# design.net
KiCad netlist of a schematic drawn in Altium Designer
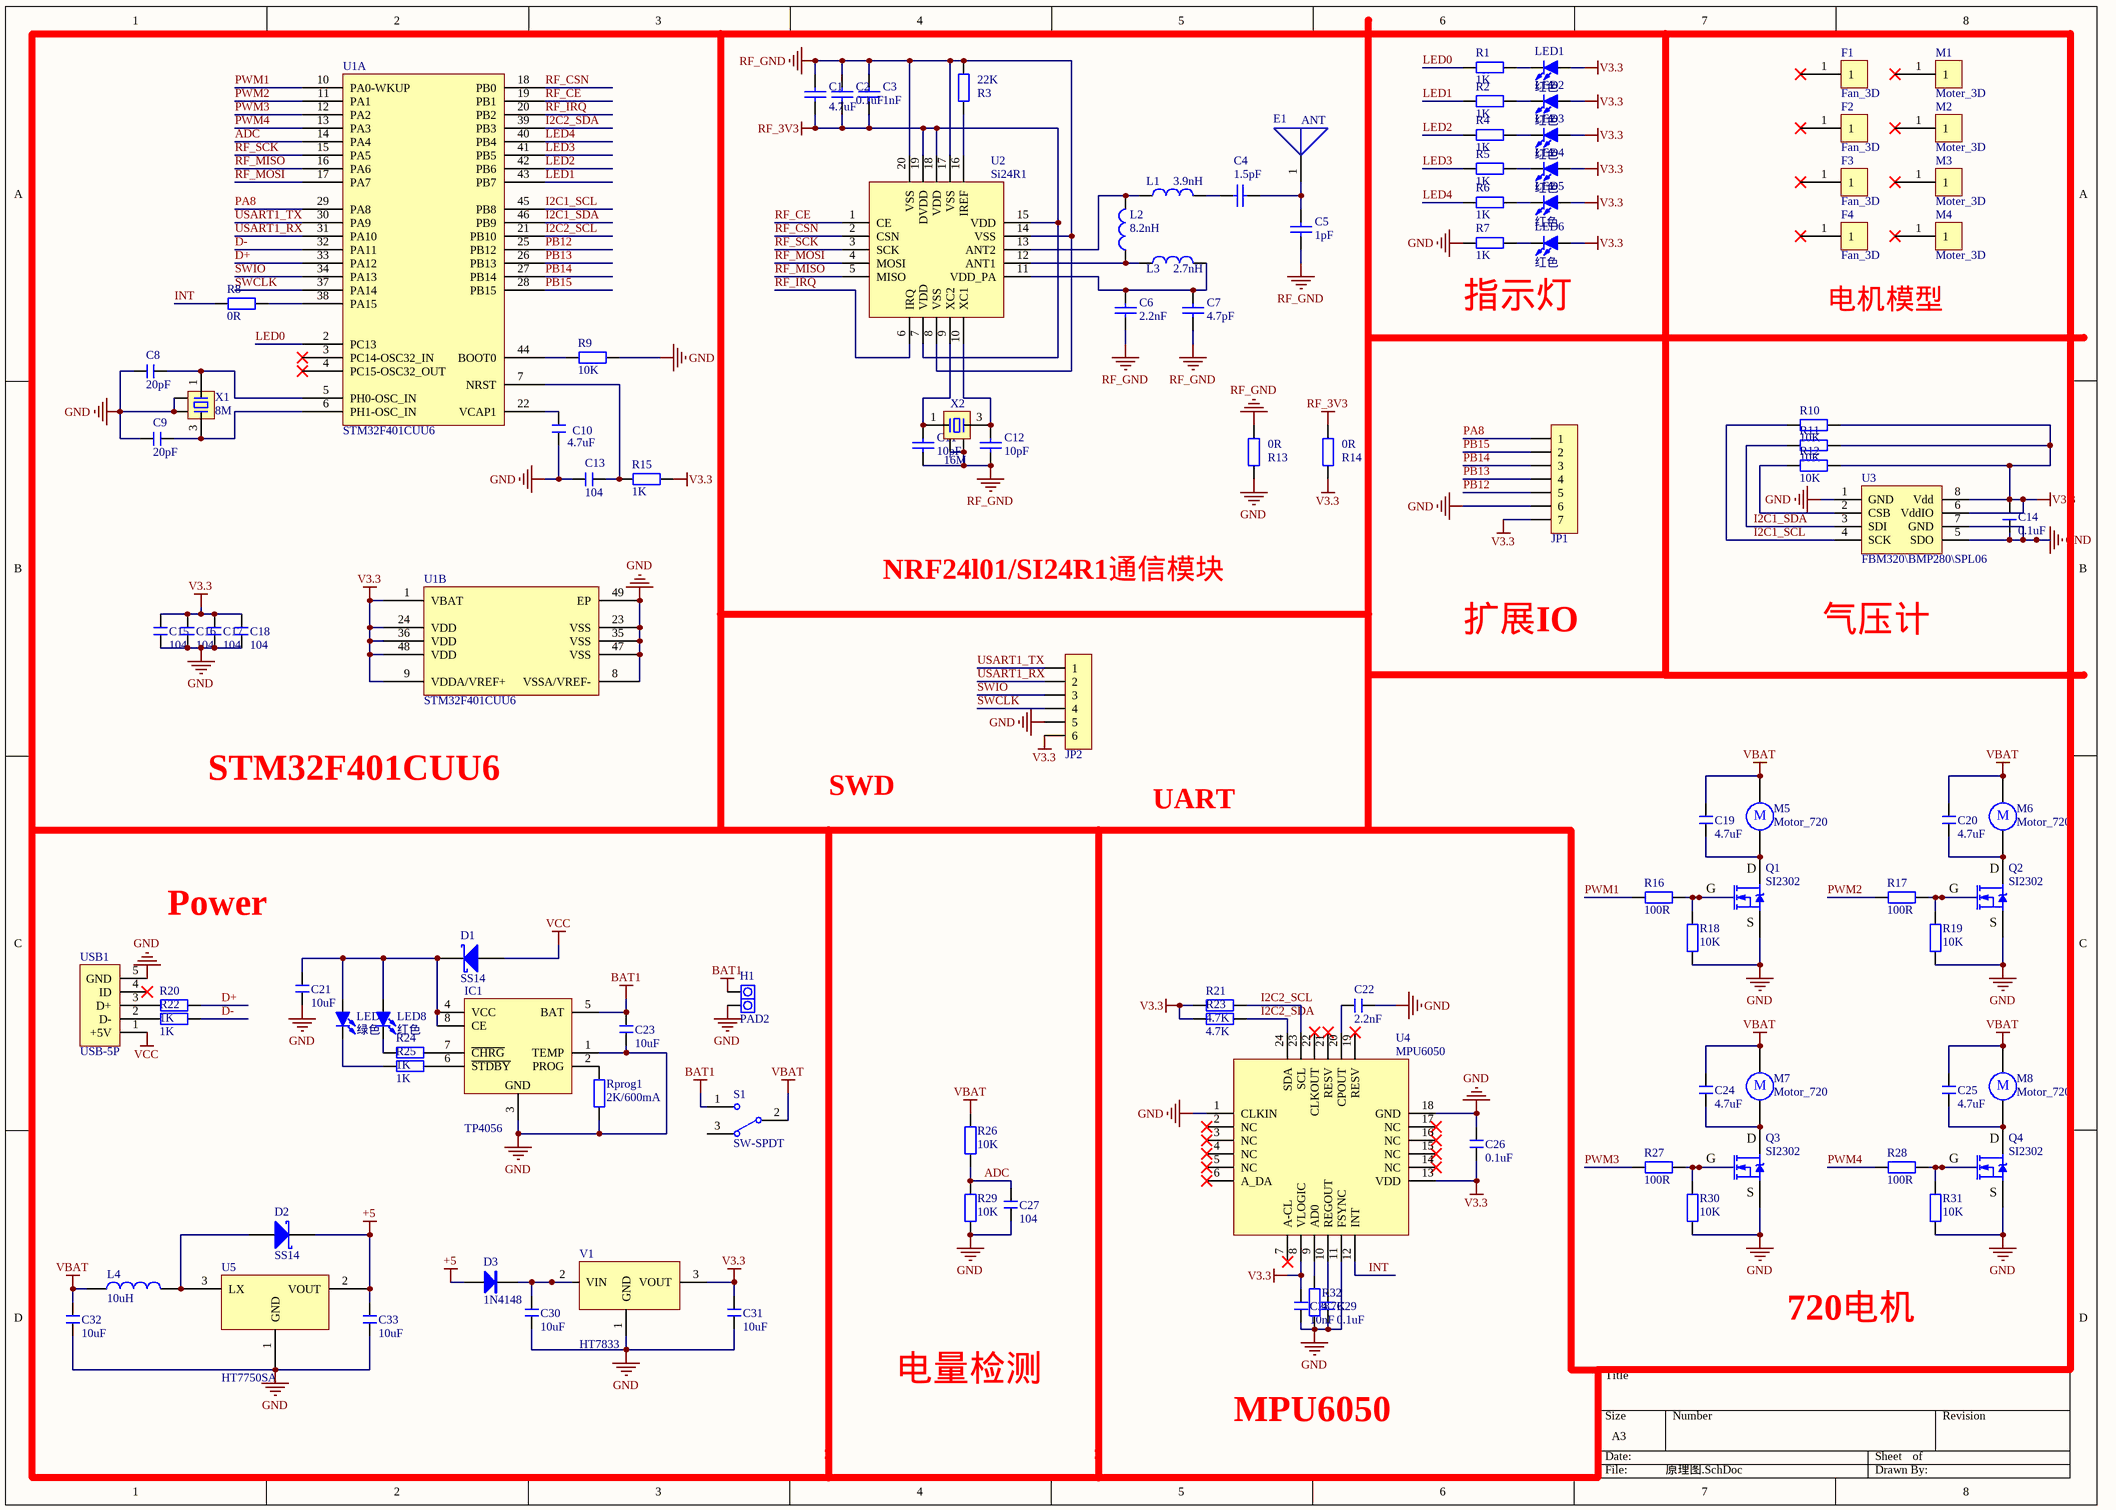
[diagram p0: 原理图.SchDoc]

(export (version "E")
  (design (tool "Eeschema 10.0.6"))
  (components
    (comp (ref "C1")
      (value "4.7uF")
      (footprint "C 0603_L")
      (fields (field (name "Comment") "C_0603") (field (name "PUBLISHER") "Altium Limited"))
      (libsource (lib "RoboFly") (part "C_0603"))
    )
    (comp (ref "C2")
      (value "0.1uF")
      (footprint "C 0603_L")
      (fields (field (name "Comment") "C_0603") (field (name "PUBLISHER") "Altium Limited"))
      (libsource (lib "RoboFly") (part "C_0603"))
    )
    (comp (ref "C3")
      (value "1nF")
      (footprint "C 0603_L")
      (fields (field (name "Comment") "C_0603") (field (name "PUBLISHER") "Altium Limited"))
      (libsource (lib "RoboFly") (part "C_0603"))
    )
    (comp (ref "C4")
      (value "1.5pF")
      (footprint "C 0603_L")
      (fields (field (name "Comment") "C_0603") (field (name "PUBLISHER") "Altium Limited"))
      (libsource (lib "RoboFly") (part "C_0603"))
    )
    (comp (ref "C5")
      (value "1pF")
      (footprint "C 0603_L")
      (fields (field (name "Comment") "C_0603") (field (name "PUBLISHER") "Altium Limited"))
      (libsource (lib "RoboFly") (part "C_0603"))
    )
    (comp (ref "C6")
      (value "2.2nF")
      (footprint "C 0603_L")
      (fields (field (name "Comment") "C_0603") (field (name "PUBLISHER") "Altium Limited"))
      (libsource (lib "RoboFly") (part "C_0603"))
    )
    (comp (ref "C7")
      (value "4.7pF")
      (footprint "C 0603_L")
      (fields (field (name "Comment") "C_0603") (field (name "PUBLISHER") "Altium Limited"))
      (libsource (lib "RoboFly") (part "C_0603"))
    )
    (comp (ref "C8")
      (value "20pF")
      (footprint "R 0603_M")
      (description "贴片电容")
      (libsource (lib "0.1 - 电阻-电容-电感") (part "C"))
    )
    (comp (ref "C9")
      (value "20pF")
      (footprint "R 0603_M")
      (description "贴片电容")
      (libsource (lib "0.1 - 电阻-电容-电感") (part "C"))
    )
    (comp (ref "C10")
      (value "4.7uF")
      (footprint "C 0603_L")
      (description "贴片电容")
      (libsource (lib "0.1 - 电阻-电容-电感") (part "C"))
    )
    (comp (ref "C11")
      (value "10pF")
      (footprint "C 0603_L")
      (fields (field (name "Comment") "C_0603") (field (name "PUBLISHER") "Altium Limited"))
      (libsource (lib "RoboFly") (part "C_0603"))
    )
    (comp (ref "C12")
      (value "10pF")
      (footprint "C 0603_L")
      (fields (field (name "Comment") "C_0603") (field (name "PUBLISHER") "Altium Limited"))
      (libsource (lib "RoboFly") (part "C_0603"))
    )
    (comp (ref "C13")
      (value "104")
      (footprint "C 0603_L")
      (description "贴片电容")
      (libsource (lib "0.1 - 电阻-电容-电感") (part "C"))
    )
    (comp (ref "C14")
      (value "0.1uF")
      (footprint "C 0603_L")
      (description "贴片电容")
      (libsource (lib "0.1 - 电阻-电容-电感") (part "C"))
    )
    (comp (ref "C15")
      (value "104")
      (footprint "C 0603_L")
      (description "贴片电容")
      (libsource (lib "0.1 - 电阻-电容-电感") (part "C"))
    )
    (comp (ref "C16")
      (value "104")
      (footprint "C 0603_L")
      (description "贴片电容")
      (libsource (lib "0.1 - 电阻-电容-电感") (part "C"))
    )
    (comp (ref "C17")
      (value "104")
      (footprint "C 0603_L")
      (description "贴片电容")
      (libsource (lib "0.1 - 电阻-电容-电感") (part "C"))
    )
    (comp (ref "C18")
      (value "104")
      (footprint "C 0603_L")
      (description "贴片电容")
      (libsource (lib "0.1 - 电阻-电容-电感") (part "C"))
    )
    (comp (ref "C19")
      (value "4.7uF")
      (footprint "C 0603_L")
      (description "贴片电容")
      (libsource (lib "0.1 - 电阻-电容-电感") (part "C"))
    )
    (comp (ref "C20")
      (value "4.7uF")
      (footprint "C 0603_L")
      (description "贴片电容")
      (libsource (lib "0.1 - 电阻-电容-电感") (part "C"))
    )
    (comp (ref "C21")
      (value "10uF")
      (footprint "C 0603_L")
      (description "贴片电容")
      (libsource (lib "0.1 - 电阻-电容-电感") (part "C"))
    )
    (comp (ref "C22")
      (value "2.2nF")
      (footprint "C 0603_L")
      (description "贴片电容")
      (libsource (lib "0.1 - 电阻-电容-电感") (part "C"))
    )
    (comp (ref "C23")
      (value "10uF")
      (footprint "C 0603_L")
      (description "贴片电容")
      (libsource (lib "0.1 - 电阻-电容-电感") (part "C"))
    )
    (comp (ref "C24")
      (value "4.7uF")
      (footprint "C 0603_L")
      (description "贴片电容")
      (libsource (lib "0.1 - 电阻-电容-电感") (part "C"))
    )
    (comp (ref "C25")
      (value "4.7uF")
      (footprint "C 0603_L")
      (description "贴片电容")
      (libsource (lib "0.1 - 电阻-电容-电感") (part "C"))
    )
    (comp (ref "C26")
      (value "0.1uF")
      (footprint "C 0603_L")
      (description "贴片电容")
      (libsource (lib "0.1 - 电阻-电容-电感") (part "C"))
    )
    (comp (ref "C27")
      (value "104")
      (footprint "C 0603_L")
      (description "贴片电容")
      (libsource (lib "0.1 - 电阻-电容-电感") (part "C"))
    )
    (comp (ref "C28")
      (value "10nF")
      (footprint "C 0603_L")
      (description "贴片电容")
      (libsource (lib "0.1 - 电阻-电容-电感") (part "C"))
    )
    (comp (ref "C29")
      (value "0.1uF")
      (footprint "C 0603_L")
      (description "贴片电容")
      (libsource (lib "0.1 - 电阻-电容-电感") (part "C"))
    )
    (comp (ref "C30")
      (value "10uF")
      (footprint "C 0603_L")
      (description "贴片电容")
      (libsource (lib "0.1 - 电阻-电容-电感") (part "C"))
    )
    (comp (ref "C31")
      (value "10uF")
      (footprint "C 0603_L")
      (description "贴片电容")
      (libsource (lib "0.1 - 电阻-电容-电感") (part "C"))
    )
    (comp (ref "C32")
      (value "10uF")
      (footprint "C 0603_L")
      (description "贴片电容")
      (libsource (lib "0.1 - 电阻-电容-电感") (part "C"))
    )
    (comp (ref "C33")
      (value "10uF")
      (footprint "C 0603_L")
      (description "贴片电容")
      (libsource (lib "0.1 - 电阻-电容-电感") (part "C"))
    )
    (comp (ref "D1")
      (value "SS14")
      (footprint "SMA")
      (description "肖特基二极管")
      (libsource (lib "0.2 -  二极管-整流桥") (part "SS14"))
    )
    (comp (ref "D2")
      (value "SS14")
      (footprint "SMA")
      (description "肖特基二极管")
      (libsource (lib "0.2 -  二极管-整流桥") (part "SS14"))
    )
    (comp (ref "D3")
      (value "1N4148")
      (footprint "MINI_MELF (LL34)")
      (description "开关二极管")
      (libsource (lib "0.2 -  二极管-整流桥") (part "1N4148"))
    )
    (comp (ref "E1")
      (value "ANT")
      (footprint "ANT - duplicate")
      (fields (field (name "PUBLISHER") "mazhongwei"))
      (libsource (lib "RoboFly") (part "ANT"))
    )
    (comp (ref "F1") (value "Fan_3D") (footprint "BLADEB") (libsource (lib "Schlib1") (part "Fan_3D")))
    (comp (ref "F2") (value "Fan_3D") (footprint "BLADEB") (libsource (lib "Schlib1") (part "Fan_3D")))
    (comp (ref "F3") (value "Fan_3D") (footprint "BLADEB") (libsource (lib "Schlib1") (part "Fan_3D")))
    (comp (ref "F4") (value "Fan_3D") (footprint "BLADEB") (libsource (lib "Schlib1") (part "Fan_3D")))
    (comp (ref "H1")
      (value "PAD2")
      (footprint "PAD2-2.54")
      (description "引线焊盘")
      (fields (field (name "版权归属") "封装库来自淘宝 ID：黄晶宝石"))
      (libsource (lib "4.1 - 未分类器件") (part "PAD2"))
    )
    (comp (ref "IC1")
      (value "TP4056")
      (footprint "SOP8_N")
      (description "锂电池充电管理")
      (libsource (lib "1.1 - 电源类芯片") (part "TP4056"))
    )
    (comp (ref "JP1")
      (value "HDR-1X7")
      (footprint "HDR2.54-LI-7P")
      (description "7P接插件")
      (fields (field (name "版权归属") "封装库来自淘宝 ID：黄晶宝石"))
      (libsource (lib "5.3 - 接插件-脚距2.54 (100mil) ") (part "Header 7"))
    )
    (comp (ref "JP2")
      (value "HDR-1X6")
      (footprint "SH1.0-6P")
      (description "6P接插件")
      (fields (field (name "版权归属") "封装库来自淘宝 ID：黄晶宝石"))
      (libsource (lib "5.3 - 接插件-脚距2.54 (100mil) ") (part "Header 6"))
    )
    (comp (ref "L1")
      (value "3.9nH")
      (footprint "L 0603")
      (description "电感")
      (fields (field (name "Comment") "Inductor") (field (name "PUBLISHER") "Altium Limited"))
      (libsource (lib "RoboFly") (part "Inductor_1"))
    )
    (comp (ref "L2")
      (value "8.2nH")
      (footprint "L 0603")
      (description "电感")
      (fields (field (name "Comment") "Inductor") (field (name "PUBLISHER") "Altium Limited"))
      (libsource (lib "RoboFly") (part "Inductor_1"))
    )
    (comp (ref "L3")
      (value "2.7nH")
      (footprint "L 0603")
      (description "电感")
      (fields (field (name "Comment") "Inductor") (field (name "PUBLISHER") "Altium Limited"))
      (libsource (lib "RoboFly") (part "Inductor_1"))
    )
    (comp (ref "L4")
      (value "10uH")
      (footprint "L 0805")
      (description "小功率贴片电感")
      (libsource (lib "0.1 - 电阻-电容-电感") (part "L"))
    )
    (comp (ref "LED1")
      (value "红色")
      (footprint "LED 0603R")
      (description "贴片LED")
      (fields (field (name "版权归属") "封装库来自淘宝 ID：黄晶宝石"))
      (libsource (lib "0.3 - LED发光二极管") (part "LED-SMD"))
    )
    (comp (ref "LED2")
      (value "红色")
      (footprint "LED 0603R")
      (description "贴片LED")
      (fields (field (name "版权归属") "封装库来自淘宝 ID：黄晶宝石"))
      (libsource (lib "0.3 - LED发光二极管") (part "LED-SMD"))
    )
    (comp (ref "LED3")
      (value "红色")
      (footprint "LED 0603R")
      (description "贴片LED")
      (fields (field (name "版权归属") "封装库来自淘宝 ID：黄晶宝石"))
      (libsource (lib "0.3 - LED发光二极管") (part "LED-SMD"))
    )
    (comp (ref "LED4")
      (value "红色")
      (footprint "LED 0603R")
      (description "贴片LED")
      (fields (field (name "版权归属") "封装库来自淘宝 ID：黄晶宝石"))
      (libsource (lib "0.3 - LED发光二极管") (part "LED-SMD"))
    )
    (comp (ref "LED5")
      (value "红色")
      (footprint "LED 0603R")
      (description "贴片LED")
      (fields (field (name "版权归属") "封装库来自淘宝 ID：黄晶宝石"))
      (libsource (lib "0.3 - LED发光二极管") (part "LED-SMD"))
    )
    (comp (ref "LED6")
      (value "红色")
      (footprint "LED 0603R")
      (description "贴片LED")
      (fields (field (name "版权归属") "封装库来自淘宝 ID：黄晶宝石"))
      (libsource (lib "0.3 - LED发光二极管") (part "LED-SMD"))
    )
    (comp (ref "LED7")
      (value "绿色")
      (footprint "LED 0603G")
      (description "贴片LED")
      (fields (field (name "版权归属") "封装库来自淘宝 ID：黄晶宝石"))
      (libsource (lib "0.3 - LED发光二极管") (part "LED-SMD"))
    )
    (comp (ref "LED8")
      (value "红色")
      (footprint "LED 0603R")
      (description "贴片LED")
      (fields (field (name "版权归属") "封装库来自淘宝 ID：黄晶宝石"))
      (libsource (lib "0.3 - LED发光二极管") (part "LED-SMD"))
    )
    (comp (ref "M1") (value "Moter_3D") (footprint "720Motor") (libsource (lib "Schlib1") (part "Moter_3D")))
    (comp (ref "M2") (value "Moter_3D") (footprint "720Motor") (libsource (lib "Schlib1") (part "Moter_3D")))
    (comp (ref "M3") (value "Moter_3D") (footprint "720Motor") (libsource (lib "Schlib1") (part "Moter_3D")))
    (comp (ref "M4") (value "Moter_3D") (footprint "720Motor") (libsource (lib "Schlib1") (part "Moter_3D")))
    (comp (ref "M5")
      (value "Motor_720")
      (footprint "MOTOR")
      (description "Motor, General Kind")
      (fields (field (name "PUBLISHER") "mazhongwei"))
      (libsource (lib "Schlib1") (part "Motor_720"))
    )
    (comp (ref "M6")
      (value "Motor_720")
      (footprint "MOTOR")
      (description "Motor, General Kind")
      (fields (field (name "PUBLISHER") "mazhongwei"))
      (libsource (lib "Schlib1") (part "Motor_720"))
    )
    (comp (ref "M7")
      (value "Motor_720")
      (footprint "MOTOR")
      (description "Motor, General Kind")
      (fields (field (name "PUBLISHER") "mazhongwei"))
      (libsource (lib "Schlib1") (part "Motor_720"))
    )
    (comp (ref "M8")
      (value "Motor_720")
      (footprint "MOTOR")
      (description "Motor, General Kind")
      (fields (field (name "PUBLISHER") "mazhongwei"))
      (libsource (lib "Schlib1") (part "Motor_720"))
    )
    (comp (ref "Q1")
      (value "SI2302")
      (footprint "SOT23-3N")
      (description "N沟道场效应管")
      (libsource (lib "0.5 - 场效应管-可控硅") (part "SI2302"))
    )
    (comp (ref "Q2")
      (value "SI2302")
      (footprint "SOT23-3N")
      (description "N沟道场效应管")
      (libsource (lib "0.5 - 场效应管-可控硅") (part "SI2302"))
    )
    (comp (ref "Q3")
      (value "SI2302")
      (footprint "SOT23-3N")
      (description "N沟道场效应管")
      (libsource (lib "0.5 - 场效应管-可控硅") (part "SI2302"))
    )
    (comp (ref "Q4")
      (value "SI2302")
      (footprint "SOT23-3N")
      (description "N沟道场效应管")
      (libsource (lib "0.5 - 场效应管-可控硅") (part "SI2302"))
    )
    (comp (ref "R1")
      (value "1K")
      (footprint "R 0603_L")
      (description "贴片电阻")
      (fields (field (name "版权归属") "来自淘宝 ID：黄晶宝石"))
      (libsource (lib "0.1 - 电阻-电容-电感") (part "R"))
    )
    (comp (ref "R2")
      (value "1K")
      (footprint "R 0603_L")
      (description "贴片电阻")
      (fields (field (name "版权归属") "来自淘宝 ID：黄晶宝石"))
      (libsource (lib "0.1 - 电阻-电容-电感") (part "R"))
    )
    (comp (ref "R3")
      (value "22K")
      (footprint "R 0603_L")
      (fields (field (name "Comment") "R_0603") (field (name "PUBLISHER") "Altium Limited"))
      (libsource (lib "RoboFly") (part "R_0603"))
    )
    (comp (ref "R4")
      (value "1K")
      (footprint "R 0603_L")
      (description "贴片电阻")
      (fields (field (name "版权归属") "来自淘宝 ID：黄晶宝石"))
      (libsource (lib "0.1 - 电阻-电容-电感") (part "R"))
    )
    (comp (ref "R5")
      (value "1K")
      (footprint "R 0603_L")
      (description "贴片电阻")
      (fields (field (name "版权归属") "来自淘宝 ID：黄晶宝石"))
      (libsource (lib "0.1 - 电阻-电容-电感") (part "R"))
    )
    (comp (ref "R6")
      (value "1K")
      (footprint "R 0603_L")
      (description "贴片电阻")
      (fields (field (name "版权归属") "来自淘宝 ID：黄晶宝石"))
      (libsource (lib "0.1 - 电阻-电容-电感") (part "R"))
    )
    (comp (ref "R7")
      (value "1K")
      (footprint "R 0603_L")
      (description "贴片电阻")
      (fields (field (name "版权归属") "来自淘宝 ID：黄晶宝石"))
      (libsource (lib "0.1 - 电阻-电容-电感") (part "R"))
    )
    (comp (ref "R8")
      (value "0R")
      (footprint "R 0603_L")
      (description "贴片电阻")
      (fields (field (name "版权归属") "来自淘宝 ID：黄晶宝石"))
      (libsource (lib "0.1 - 电阻-电容-电感") (part "R"))
    )
    (comp (ref "R9")
      (value "10K")
      (footprint "R 0603_L")
      (description "贴片电阻")
      (fields (field (name "版权归属") "来自淘宝 ID：黄晶宝石"))
      (libsource (lib "0.1 - 电阻-电容-电感") (part "R"))
    )
    (comp (ref "R10")
      (value "10K")
      (footprint "R 0603_L")
      (description "贴片电阻")
      (fields (field (name "版权归属") "来自淘宝 ID：黄晶宝石"))
      (libsource (lib "0.1 - 电阻-电容-电感") (part "R"))
    )
    (comp (ref "R11")
      (value "10K")
      (footprint "R 0603_L")
      (description "贴片电阻")
      (fields (field (name "版权归属") "来自淘宝 ID：黄晶宝石"))
      (libsource (lib "0.1 - 电阻-电容-电感") (part "R"))
    )
    (comp (ref "R12")
      (value "10K")
      (footprint "R 0603_L")
      (description "贴片电阻")
      (fields (field (name "版权归属") "来自淘宝 ID：黄晶宝石"))
      (libsource (lib "0.1 - 电阻-电容-电感") (part "R"))
    )
    (comp (ref "R13")
      (value "0R")
      (footprint "R 0603_L")
      (fields (field (name "Comment") "R_0603") (field (name "PUBLISHER") "Altium Limited"))
      (libsource (lib "RoboFly") (part "R_0603"))
    )
    (comp (ref "R14")
      (value "0R")
      (footprint "R 0603_L")
      (fields (field (name "Comment") "R_0603") (field (name "PUBLISHER") "Altium Limited"))
      (libsource (lib "RoboFly") (part "R_0603"))
    )
    (comp (ref "R15")
      (value "1K")
      (footprint "R 0603_L")
      (description "贴片电阻")
      (fields (field (name "版权归属") "来自淘宝 ID：黄晶宝石"))
      (libsource (lib "0.1 - 电阻-电容-电感") (part "R"))
    )
    (comp (ref "R16")
      (value "100R")
      (footprint "R 0603_L")
      (description "贴片电阻")
      (fields (field (name "版权归属") "来自淘宝 ID：黄晶宝石"))
      (libsource (lib "0.1 - 电阻-电容-电感") (part "R"))
    )
    (comp (ref "R17")
      (value "100R")
      (footprint "R 0603_L")
      (description "贴片电阻")
      (fields (field (name "版权归属") "来自淘宝 ID：黄晶宝石"))
      (libsource (lib "0.1 - 电阻-电容-电感") (part "R"))
    )
    (comp (ref "R18")
      (value "10K")
      (footprint "R 0603_L")
      (description "贴片电阻")
      (fields (field (name "版权归属") "来自淘宝 ID：黄晶宝石"))
      (libsource (lib "0.1 - 电阻-电容-电感") (part "R"))
    )
    (comp (ref "R19")
      (value "10K")
      (footprint "R 0603_L")
      (description "贴片电阻")
      (fields (field (name "版权归属") "来自淘宝 ID：黄晶宝石"))
      (libsource (lib "0.1 - 电阻-电容-电感") (part "R"))
    )
    (comp (ref "R20")
      (value "1K")
      (footprint "R 0603_L")
      (description "贴片电阻")
      (fields (field (name "版权归属") "来自淘宝 ID：黄晶宝石"))
      (libsource (lib "0.1 - 电阻-电容-电感") (part "R"))
    )
    (comp (ref "R21")
      (value "4.7K")
      (footprint "R 0603_L")
      (description "贴片电阻")
      (fields (field (name "版权归属") "来自淘宝 ID：黄晶宝石"))
      (libsource (lib "0.1 - 电阻-电容-电感") (part "R"))
    )
    (comp (ref "R22")
      (value "1K")
      (footprint "R 0603_L")
      (description "贴片电阻")
      (fields (field (name "版权归属") "来自淘宝 ID：黄晶宝石"))
      (libsource (lib "0.1 - 电阻-电容-电感") (part "R"))
    )
    (comp (ref "R23")
      (value "4.7K")
      (footprint "R 0603_L")
      (description "贴片电阻")
      (fields (field (name "版权归属") "来自淘宝 ID：黄晶宝石"))
      (libsource (lib "0.1 - 电阻-电容-电感") (part "R"))
    )
    (comp (ref "R24")
      (value "1K")
      (footprint "R 0603_L")
      (description "贴片电阻")
      (fields (field (name "版权归属") "来自淘宝 ID：黄晶宝石"))
      (libsource (lib "0.1 - 电阻-电容-电感") (part "R"))
    )
    (comp (ref "R25")
      (value "1K")
      (footprint "R 0603_L")
      (description "贴片电阻")
      (fields (field (name "版权归属") "来自淘宝 ID：黄晶宝石"))
      (libsource (lib "0.1 - 电阻-电容-电感") (part "R"))
    )
    (comp (ref "R26")
      (value "10K")
      (footprint "R 0603_L")
      (description "贴片电阻")
      (fields (field (name "版权归属") "来自淘宝 ID：黄晶宝石"))
      (libsource (lib "0.1 - 电阻-电容-电感") (part "R"))
    )
    (comp (ref "R27")
      (value "100R")
      (footprint "R 0603_L")
      (description "贴片电阻")
      (fields (field (name "版权归属") "来自淘宝 ID：黄晶宝石"))
      (libsource (lib "0.1 - 电阻-电容-电感") (part "R"))
    )
    (comp (ref "R28")
      (value "100R")
      (footprint "R 0603_L")
      (description "贴片电阻")
      (fields (field (name "版权归属") "来自淘宝 ID：黄晶宝石"))
      (libsource (lib "0.1 - 电阻-电容-电感") (part "R"))
    )
    (comp (ref "R29")
      (value "10K")
      (footprint "R 0603_L")
      (description "贴片电阻")
      (fields (field (name "版权归属") "来自淘宝 ID：黄晶宝石"))
      (libsource (lib "0.1 - 电阻-电容-电感") (part "R"))
    )
    (comp (ref "R30")
      (value "10K")
      (footprint "R 0603_L")
      (description "贴片电阻")
      (fields (field (name "版权归属") "来自淘宝 ID：黄晶宝石"))
      (libsource (lib "0.1 - 电阻-电容-电感") (part "R"))
    )
    (comp (ref "R31")
      (value "10K")
      (footprint "R 0603_L")
      (description "贴片电阻")
      (fields (field (name "版权归属") "来自淘宝 ID：黄晶宝石"))
      (libsource (lib "0.1 - 电阻-电容-电感") (part "R"))
    )
    (comp (ref "R32")
      (value "4.7K")
      (footprint "R 0603_L")
      (description "贴片电阻")
      (fields (field (name "版权归属") "来自淘宝 ID：黄晶宝石"))
      (libsource (lib "0.1 - 电阻-电容-电感") (part "R"))
    )
    (comp (ref "Rprog1")
      (value "2K/600mA")
      (footprint "R 0603_M")
      (description "贴片电阻")
      (fields (field (name "版权归属") "来自淘宝 ID：黄晶宝石"))
      (libsource (lib "0.1 - 电阻-电容-电感") (part "R"))
    )
    (comp (ref "S1")
      (value "SW-SPDT")
      (footprint "SWITCH_PWR")
      (description "SPDT Subminiature Toggle Switch, Right Angle Mounting, Vertical Actuation")
      (fields (field (name "PUBLISHER") "mazhongwei"))
      (libsource (lib "Schlib1") (part "SW-SPDT"))
    )
    (comp (ref "U1")
      (value "STM32F401CUU6")
      (footprint "QFN48 7X7_M")
      (libsource (lib "Schlib1") (part "STM32F401CUU6"))
    )
    (comp (ref "U2") (value "Si24R1") (footprint "QFN20 4x4_M") (libsource (lib "RoboFly") (part "nRF24L01")))
    (comp (ref "U3")
      (value "FBM32~{0}BMP28~{0}SPL06")
      (footprint "LGA-2_5X2MM")
      (description "气压计")
      (fields (field (name "PUBLISHER") "mazhongwei"))
      (libsource (lib "Schlib1") (part "FBM320"))
    )
    (comp (ref "U4") (value "MPU6050") (footprint "QFN24 4x4_M") (libsource (lib "RoboFly") (part "MPU6050")))
    (comp (ref "U5")
      (value "HT7750SA")
      (footprint "SOT-89(SOT-89-3)")
      (libsource (lib "Schlib1") (part "HT7750SA"))
    )
    (comp (ref "USB1")
      (value "USB-5P")
      (footprint "USB-MICRO_D")
      (description "微型USB母座")
      (libsource (lib "0.8 - 网口-音频插座") (part "USB-5P"))
    )
    (comp (ref "V1")
      (value "HT7833")
      (footprint "SOT89_M")
      (description "LDO线性稳压芯片")
      (fields (field (name "版权归属") "封装库来自淘宝 ID：黄晶宝石"))
      (libsource (lib "1.1 - 电源类芯片") (part "HT71xx"))
    )
    (comp (ref "X1")
      (value "8M")
      (footprint "OSC 3225-4P")
      (description "4脚无源晶振")
      (fields (field (name "版权归属") "源创客"))
      (libsource (lib "2.0 - 保险丝-晶振-光耦") (part "XTAL-4P"))
    )
    (comp (ref "X2")
      (value "16M")
      (footprint "OSC 3225-4P")
      (description "4脚无源晶振")
      (fields (field (name "版权归属") "源创客"))
      (libsource (lib "") (part "XTAL-4P_1"))
    )
  )
  (nets
    (net (code "1") (name "+5") (class "Default")
      (node (ref "C33") (pin "2") (pinfunction "2_2") (pintype "passive"))
      (node (ref "D2") (pin "2") (pinfunction "K_2") (pintype "passive"))
      (node (ref "D3") (pin "1") (pinfunction "A_1") (pintype "passive"))
      (node (ref "U5") (pin "2") (pinfunction "VOUT_2") (pintype "passive"))
    )
    (net (code "2") (name "/ADC") (class "Default")
      (node (ref "C27") (pin "2") (pinfunction "2_2") (pintype "passive"))
      (node (ref "R26") (pin "1") (pinfunction "1_1") (pintype "passive"))
      (node (ref "R29") (pin "2") (pinfunction "2_2") (pintype "passive"))
      (node (ref "U1") (pin "14") (pinfunction "PA4_14") (pintype "passive"))
    )
    (net (code "3") (name "/D+") (class "Default")
      (node (ref "R20") (pin "2") (pinfunction "2_2") (pintype "passive"))
      (node (ref "U1") (pin "33") (pinfunction "PA12_33") (pintype "passive"))
    )
    (net (code "4") (name "/D-") (class "Default")
      (node (ref "R22") (pin "2") (pinfunction "2_2") (pintype "passive"))
      (node (ref "U1") (pin "32") (pinfunction "PA11_32") (pintype "passive"))
    )
    (net (code "5") (name "/I2C1_SCL") (class "Default")
      (node (ref "R10") (pin "1") (pinfunction "1_1") (pintype "passive"))
      (node (ref "U1") (pin "45") (pinfunction "PB8_45") (pintype "passive"))
      (node (ref "U3") (pin "4") (pinfunction "SCK_4") (pintype "passive"))
    )
    (net (code "6") (name "/I2C1_SDA") (class "Default")
      (node (ref "R11") (pin "1") (pinfunction "1_1") (pintype "passive"))
      (node (ref "U1") (pin "46") (pinfunction "PB9_46") (pintype "passive"))
      (node (ref "U3") (pin "3") (pinfunction "SDI_3") (pintype "passive"))
    )
    (net (code "7") (name "/I2C2_SCL") (class "Default")
      (node (ref "R21") (pin "1") (pinfunction "1_1") (pintype "passive"))
      (node (ref "U1") (pin "21") (pinfunction "PB10_21") (pintype "passive"))
      (node (ref "U4") (pin "23") (pinfunction "SCL_23") (pintype "passive"))
    )
    (net (code "8") (name "/I2C2_SDA") (class "Default")
      (node (ref "R23") (pin "1") (pinfunction "1_1") (pintype "passive"))
      (node (ref "U1") (pin "39") (pinfunction "PB3_39") (pintype "passive"))
      (node (ref "U4") (pin "24") (pinfunction "SDA_24") (pintype "passive"))
    )
    (net (code "9") (name "/INT") (class "Default")
      (node (ref "R8") (pin "1") (pinfunction "1_1") (pintype "passive"))
      (node (ref "U4") (pin "12") (pinfunction "INT_12") (pintype "passive"))
    )
    (net (code "10") (name "/LED0") (class "Default")
      (node (ref "R1") (pin "2") (pinfunction "2_2") (pintype "passive"))
      (node (ref "U1") (pin "2") (pinfunction "PC13_2") (pintype "passive"))
    )
    (net (code "11") (name "/LED1") (class "Default")
      (node (ref "R2") (pin "2") (pinfunction "2_2") (pintype "passive"))
      (node (ref "U1") (pin "43") (pinfunction "PB7_43") (pintype "passive"))
    )
    (net (code "12") (name "/LED2") (class "Default")
      (node (ref "R4") (pin "2") (pinfunction "2_2") (pintype "passive"))
      (node (ref "U1") (pin "42") (pinfunction "PB6_42") (pintype "passive"))
    )
    (net (code "13") (name "/LED3") (class "Default")
      (node (ref "R5") (pin "2") (pinfunction "2_2") (pintype "passive"))
      (node (ref "U1") (pin "41") (pinfunction "PB5_41") (pintype "passive"))
    )
    (net (code "14") (name "/LED4") (class "Default")
      (node (ref "R6") (pin "2") (pinfunction "2_2") (pintype "passive"))
      (node (ref "U1") (pin "40") (pinfunction "PB4_40") (pintype "passive"))
    )
    (net (code "15") (name "/PA8") (class "Default")
      (node (ref "JP1") (pin "1") (pinfunction "1_1") (pintype "passive"))
      (node (ref "U1") (pin "29") (pinfunction "PA8_29") (pintype "passive"))
    )
    (net (code "16") (name "/PB12") (class "Default")
      (node (ref "JP1") (pin "5") (pinfunction "5_5") (pintype "passive"))
      (node (ref "U1") (pin "25") (pinfunction "PB12_25") (pintype "passive"))
    )
    (net (code "17") (name "/PB13") (class "Default")
      (node (ref "JP1") (pin "4") (pinfunction "4_4") (pintype "passive"))
      (node (ref "U1") (pin "26") (pinfunction "PB13_26") (pintype "passive"))
    )
    (net (code "18") (name "/PB14") (class "Default")
      (node (ref "JP1") (pin "3") (pinfunction "3_3") (pintype "passive"))
      (node (ref "U1") (pin "27") (pinfunction "PB14_27") (pintype "passive"))
    )
    (net (code "19") (name "/PB15") (class "Default")
      (node (ref "JP1") (pin "2") (pinfunction "2_2") (pintype "passive"))
      (node (ref "U1") (pin "28") (pinfunction "PB15_28") (pintype "passive"))
    )
    (net (code "20") (name "/PWM1") (class "Default")
      (node (ref "R16") (pin "2") (pinfunction "2_2") (pintype "passive"))
      (node (ref "U1") (pin "10") (pinfunction "PA0-WKUP_10") (pintype "passive"))
    )
    (net (code "21") (name "/PWM2") (class "Default")
      (node (ref "R17") (pin "2") (pinfunction "2_2") (pintype "passive"))
      (node (ref "U1") (pin "11") (pinfunction "PA1_11") (pintype "passive"))
    )
    (net (code "22") (name "/PWM3") (class "Default")
      (node (ref "R27") (pin "2") (pinfunction "2_2") (pintype "passive"))
      (node (ref "U1") (pin "12") (pinfunction "PA2_12") (pintype "passive"))
    )
    (net (code "23") (name "/PWM4") (class "Default")
      (node (ref "R28") (pin "2") (pinfunction "2_2") (pintype "passive"))
      (node (ref "U1") (pin "13") (pinfunction "PA3_13") (pintype "passive"))
    )
    (net (code "24") (name "/RF_CE") (class "Default")
      (node (ref "U1") (pin "19") (pinfunction "PB1_19") (pintype "passive"))
      (node (ref "U2") (pin "1") (pinfunction "CE_1") (pintype "passive"))
    )
    (net (code "25") (name "/RF_CSN") (class "Default")
      (node (ref "U1") (pin "18") (pinfunction "PB0_18") (pintype "passive"))
      (node (ref "U2") (pin "2") (pinfunction "CSN_2") (pintype "passive"))
    )
    (net (code "26") (name "/RF_IRQ") (class "Default")
      (node (ref "U1") (pin "20") (pinfunction "PB2_20") (pintype "passive"))
      (node (ref "U2") (pin "6") (pinfunction "IRQ_6") (pintype "passive"))
    )
    (net (code "27") (name "/RF_MISO") (class "Default")
      (node (ref "U1") (pin "16") (pinfunction "PA6_16") (pintype "passive"))
      (node (ref "U2") (pin "5") (pinfunction "MISO_5") (pintype "passive"))
    )
    (net (code "28") (name "/RF_MOSI") (class "Default")
      (node (ref "U1") (pin "17") (pinfunction "PA7_17") (pintype "passive"))
      (node (ref "U2") (pin "4") (pinfunction "MOSI_4") (pintype "passive"))
    )
    (net (code "29") (name "/RF_SCK") (class "Default")
      (node (ref "U1") (pin "15") (pinfunction "PA5_15") (pintype "passive"))
      (node (ref "U2") (pin "3") (pinfunction "SCK_3") (pintype "passive"))
    )
    (net (code "30") (name "/SWCLK") (class "Default")
      (node (ref "JP2") (pin "4") (pinfunction "4_4") (pintype "passive"))
      (node (ref "U1") (pin "37") (pinfunction "PA14_37") (pintype "passive"))
    )
    (net (code "31") (name "/SWIO") (class "Default")
      (node (ref "JP2") (pin "3") (pinfunction "3_3") (pintype "passive"))
      (node (ref "U1") (pin "34") (pinfunction "PA13_34") (pintype "passive"))
    )
    (net (code "32") (name "/USART1_RX") (class "Default")
      (node (ref "JP2") (pin "2") (pinfunction "2_2") (pintype "passive"))
      (node (ref "U1") (pin "31") (pinfunction "PA10_31") (pintype "passive"))
    )
    (net (code "33") (name "/USART1_TX") (class "Default")
      (node (ref "JP2") (pin "1") (pinfunction "1_1") (pintype "passive"))
      (node (ref "U1") (pin "30") (pinfunction "PA9_30") (pintype "passive"))
    )
    (net (code "34") (name "BAT1") (class "Default")
      (node (ref "C23") (pin "2") (pinfunction "2_2") (pintype "passive"))
      (node (ref "H1") (pin "1") (pinfunction "1_1") (pintype "passive"))
      (node (ref "IC1") (pin "5") (pinfunction "BAT_5") (pintype "passive"))
      (node (ref "S1") (pin "1") (pinfunction "1_1") (pintype "passive"))
    )
    (net (code "35") (name "GND") (class "Default")
      (node (ref "C10") (pin "2") (pinfunction "2_2") (pintype "passive"))
      (node (ref "C13") (pin "1") (pinfunction "1_1") (pintype "passive"))
      (node (ref "C14") (pin "1") (pinfunction "1_1") (pintype "passive"))
      (node (ref "C15") (pin "1") (pinfunction "1_1") (pintype "passive"))
      (node (ref "C16") (pin "1") (pinfunction "1_1") (pintype "passive"))
      (node (ref "C17") (pin "1") (pinfunction "1_1") (pintype "passive"))
      (node (ref "C18") (pin "1") (pinfunction "1_1") (pintype "passive"))
      (node (ref "C21") (pin "1") (pinfunction "1_1") (pintype "passive"))
      (node (ref "C22") (pin "1") (pinfunction "1_1") (pintype "passive"))
      (node (ref "C23") (pin "1") (pinfunction "1_1") (pintype "passive"))
      (node (ref "C26") (pin "2") (pinfunction "2_2") (pintype "passive"))
      (node (ref "C27") (pin "1") (pinfunction "1_1") (pintype "passive"))
      (node (ref "C28") (pin "1") (pinfunction "1_1") (pintype "passive"))
      (node (ref "C29") (pin "1") (pinfunction "1_1") (pintype "passive"))
      (node (ref "C30") (pin "1") (pinfunction "1_1") (pintype "passive"))
      (node (ref "C31") (pin "1") (pinfunction "1_1") (pintype "passive"))
      (node (ref "C32") (pin "1") (pinfunction "1_1") (pintype "passive"))
      (node (ref "C33") (pin "1") (pinfunction "1_1") (pintype "passive"))
      (node (ref "C8") (pin "2") (pinfunction "2_2") (pintype "passive"))
      (node (ref "C9") (pin "2") (pinfunction "2_2") (pintype "passive"))
      (node (ref "H1") (pin "2") (pinfunction "2_2") (pintype "passive"))
      (node (ref "IC1") (pin "1") (pinfunction "TEMP_1") (pintype "passive"))
      (node (ref "IC1") (pin "3") (pinfunction "GND_3") (pintype "passive"))
      (node (ref "JP1") (pin "6") (pinfunction "6_6") (pintype "passive"))
      (node (ref "JP2") (pin "5") (pinfunction "5_5") (pintype "passive"))
      (node (ref "Q1") (pin "2") (pinfunction "S_2") (pintype "passive"))
      (node (ref "Q2") (pin "2") (pinfunction "S_2") (pintype "passive"))
      (node (ref "Q3") (pin "2") (pinfunction "S_2") (pintype "passive"))
      (node (ref "Q4") (pin "2") (pinfunction "S_2") (pintype "passive"))
      (node (ref "R13") (pin "1") (pinfunction "1_1") (pintype "passive"))
      (node (ref "R18") (pin "2") (pinfunction "2_2") (pintype "passive"))
      (node (ref "R19") (pin "2") (pinfunction "2_2") (pintype "passive"))
      (node (ref "R29") (pin "1") (pinfunction "1_1") (pintype "passive"))
      (node (ref "R30") (pin "2") (pinfunction "2_2") (pintype "passive"))
      (node (ref "R31") (pin "2") (pinfunction "2_2") (pintype "passive"))
      (node (ref "R32") (pin "2") (pinfunction "2_2") (pintype "passive"))
      (node (ref "R7") (pin "2") (pinfunction "2_2") (pintype "passive"))
      (node (ref "R9") (pin "1") (pinfunction "1_1") (pintype "passive"))
      (node (ref "Rprog1") (pin "1") (pinfunction "1_1") (pintype "passive"))
      (node (ref "U1") (pin "23") (pinfunction "VSS_23") (pintype "passive"))
      (node (ref "U1") (pin "35") (pinfunction "VSS_35") (pintype "passive"))
      (node (ref "U1") (pin "47") (pinfunction "VSS_47") (pintype "passive"))
      (node (ref "U1") (pin "49") (pinfunction "EP_49") (pintype "passive"))
      (node (ref "U1") (pin "8") (pinfunction "VSSA/VREF-_8") (pintype "passive"))
      (node (ref "U3") (pin "1") (pinfunction "GND_1") (pintype "passive"))
      (node (ref "U3") (pin "5") (pinfunction "SDO_5") (pintype "passive"))
      (node (ref "U3") (pin "7") (pinfunction "GND_7") (pintype "passive"))
      (node (ref "U4") (pin "1") (pinfunction "CLKIN_1") (pintype "passive"))
      (node (ref "U4") (pin "11") (pinfunction "FSYNC_11") (pintype "passive"))
      (node (ref "U4") (pin "18") (pinfunction "GND_18") (pintype "passive"))
      (node (ref "U5") (pin "1") (pinfunction "GND_1") (pintype "passive"))
      (node (ref "USB1") (pin "5") (pinfunction "GND_5") (pintype "passive"))
      (node (ref "V1") (pin "1") (pinfunction "GND_1") (pintype "passive"))
      (node (ref "X1") (pin "2") (pinfunction "2_2") (pintype "passive"))
      (node (ref "X1") (pin "4") (pinfunction "4_4") (pintype "passive"))
    )
    (net (code "36") (name "Net-(C4-Pad1)") (class "Default")
      (node (ref "C4") (pin "1") (pinfunction "1_1") (pintype "passive"))
      (node (ref "L1") (pin "2") (pinfunction "2_2") (pintype "passive"))
    )
    (net (code "37") (name "Net-(C4-Pad2)") (class "Default")
      (node (ref "C4") (pin "2") (pinfunction "2_2") (pintype "passive"))
      (node (ref "C5") (pin "2") (pinfunction "2_2") (pintype "passive"))
      (node (ref "E1") (pin "1") (pinfunction "1_1") (pintype "passive"))
    )
    (net (code "38") (name "Net-(D1-K)") (class "Default")
      (node (ref "C21") (pin "2") (pinfunction "2_2") (pintype "passive"))
      (node (ref "D1") (pin "2") (pinfunction "K_2") (pintype "passive"))
      (node (ref "IC1") (pin "4") (pinfunction "VCC_4") (pintype "passive"))
      (node (ref "IC1") (pin "8") (pinfunction "CE_8") (pintype "passive"))
      (node (ref "LED7") (pin "1") (pinfunction "A_1") (pintype "passive"))
      (node (ref "LED8") (pin "1") (pinfunction "A_1") (pintype "passive"))
    )
    (net (code "39") (name "Net-(D2-A)") (class "Default")
      (node (ref "D2") (pin "1") (pinfunction "A_1") (pintype "passive"))
      (node (ref "L4") (pin "2") (pinfunction "2_2") (pintype "passive"))
      (node (ref "U5") (pin "3") (pinfunction "LX_3") (pintype "passive"))
    )
    (net (code "40") (name "Net-(D3-K)") (class "Default")
      (node (ref "C30") (pin "2") (pinfunction "2_2") (pintype "passive"))
      (node (ref "D3") (pin "2") (pinfunction "K_2") (pintype "passive"))
      (node (ref "V1") (pin "2") (pinfunction "VIN_2") (pintype "passive"))
    )
    (net (code "41") (name "Net-(IC1-PROG)") (class "Default")
      (node (ref "IC1") (pin "2") (pinfunction "PROG_2") (pintype "passive"))
      (node (ref "Rprog1") (pin "2") (pinfunction "2_2") (pintype "passive"))
    )
    (net (code "42") (name "Net-(IC1-~{CHRG})") (class "Default")
      (node (ref "IC1") (pin "7") (pinfunction "~{CHRG}_7") (pintype "passive"))
      (node (ref "R24") (pin "1") (pinfunction "1_1") (pintype "passive"))
    )
    (net (code "43") (name "Net-(IC1-~{STDBY})") (class "Default")
      (node (ref "IC1") (pin "6") (pinfunction "~{STDBY}_6") (pintype "passive"))
      (node (ref "R25") (pin "2") (pinfunction "2_2") (pintype "passive"))
    )
    (net (code "44") (name "Net-(LED1-K)") (class "Default")
      (node (ref "LED1") (pin "2") (pinfunction "K_2") (pintype "passive"))
      (node (ref "R1") (pin "1") (pinfunction "1_1") (pintype "passive"))
    )
    (net (code "45") (name "Net-(LED2-K)") (class "Default")
      (node (ref "LED2") (pin "2") (pinfunction "K_2") (pintype "passive"))
      (node (ref "R2") (pin "1") (pinfunction "1_1") (pintype "passive"))
    )
    (net (code "46") (name "Net-(LED3-K)") (class "Default")
      (node (ref "LED3") (pin "2") (pinfunction "K_2") (pintype "passive"))
      (node (ref "R4") (pin "1") (pinfunction "1_1") (pintype "passive"))
    )
    (net (code "47") (name "Net-(LED4-K)") (class "Default")
      (node (ref "LED4") (pin "2") (pinfunction "K_2") (pintype "passive"))
      (node (ref "R5") (pin "1") (pinfunction "1_1") (pintype "passive"))
    )
    (net (code "48") (name "Net-(LED5-K)") (class "Default")
      (node (ref "LED5") (pin "2") (pinfunction "K_2") (pintype "passive"))
      (node (ref "R6") (pin "1") (pinfunction "1_1") (pintype "passive"))
    )
    (net (code "49") (name "Net-(LED6-K)") (class "Default")
      (node (ref "LED6") (pin "2") (pinfunction "K_2") (pintype "passive"))
      (node (ref "R7") (pin "1") (pinfunction "1_1") (pintype "passive"))
    )
    (net (code "50") (name "Net-(LED7-K)") (class "Default")
      (node (ref "LED7") (pin "2") (pinfunction "K_2") (pintype "passive"))
      (node (ref "R25") (pin "1") (pinfunction "1_1") (pintype "passive"))
    )
    (net (code "51") (name "Net-(LED8-K)") (class "Default")
      (node (ref "LED8") (pin "2") (pinfunction "K_2") (pintype "passive"))
      (node (ref "R24") (pin "2") (pinfunction "2_2") (pintype "passive"))
    )
    (net (code "52") (name "Net-(Q1-D)") (class "Default")
      (node (ref "C19") (pin "1") (pinfunction "1_1") (pintype "passive"))
      (node (ref "M5") (pin "2") (pinfunction "2_2") (pintype "passive"))
      (node (ref "Q1") (pin "3") (pinfunction "D_3") (pintype "passive"))
    )
    (net (code "53") (name "Net-(Q1-G)") (class "Default")
      (node (ref "Q1") (pin "1") (pinfunction "G_1") (pintype "passive"))
      (node (ref "R16") (pin "1") (pinfunction "1_1") (pintype "passive"))
      (node (ref "R18") (pin "1") (pinfunction "1_1") (pintype "passive"))
    )
    (net (code "54") (name "Net-(Q2-D)") (class "Default")
      (node (ref "C20") (pin "1") (pinfunction "1_1") (pintype "passive"))
      (node (ref "M6") (pin "2") (pinfunction "2_2") (pintype "passive"))
      (node (ref "Q2") (pin "3") (pinfunction "D_3") (pintype "passive"))
    )
    (net (code "55") (name "Net-(Q2-G)") (class "Default")
      (node (ref "Q2") (pin "1") (pinfunction "G_1") (pintype "passive"))
      (node (ref "R17") (pin "1") (pinfunction "1_1") (pintype "passive"))
      (node (ref "R19") (pin "1") (pinfunction "1_1") (pintype "passive"))
    )
    (net (code "56") (name "Net-(Q3-D)") (class "Default")
      (node (ref "C24") (pin "1") (pinfunction "1_1") (pintype "passive"))
      (node (ref "M7") (pin "2") (pinfunction "2_2") (pintype "passive"))
      (node (ref "Q3") (pin "3") (pinfunction "D_3") (pintype "passive"))
    )
    (net (code "57") (name "Net-(Q3-G)") (class "Default")
      (node (ref "Q3") (pin "1") (pinfunction "G_1") (pintype "passive"))
      (node (ref "R27") (pin "1") (pinfunction "1_1") (pintype "passive"))
      (node (ref "R30") (pin "1") (pinfunction "1_1") (pintype "passive"))
    )
    (net (code "58") (name "Net-(Q4-D)") (class "Default")
      (node (ref "C25") (pin "1") (pinfunction "1_1") (pintype "passive"))
      (node (ref "M8") (pin "2") (pinfunction "2_2") (pintype "passive"))
      (node (ref "Q4") (pin "3") (pinfunction "D_3") (pintype "passive"))
    )
    (net (code "59") (name "Net-(Q4-G)") (class "Default")
      (node (ref "Q4") (pin "1") (pinfunction "G_1") (pintype "passive"))
      (node (ref "R28") (pin "1") (pinfunction "1_1") (pintype "passive"))
      (node (ref "R31") (pin "1") (pinfunction "1_1") (pintype "passive"))
    )
    (net (code "60") (name "Net-(U1A-BOOT0)") (class "Default")
      (node (ref "R9") (pin "2") (pinfunction "2_2") (pintype "passive"))
      (node (ref "U1") (pin "44") (pinfunction "BOOT0_44") (pintype "passive"))
    )
    (net (code "61") (name "Net-(U1A-NRST)") (class "Default")
      (node (ref "C13") (pin "2") (pinfunction "2_2") (pintype "passive"))
      (node (ref "R15") (pin "1") (pinfunction "1_1") (pintype "passive"))
      (node (ref "U1") (pin "7") (pinfunction "NRST_7") (pintype "passive"))
    )
    (net (code "62") (name "Net-(U1A-PA15)") (class "Default")
      (node (ref "R8") (pin "2") (pinfunction "2_2") (pintype "passive"))
      (node (ref "U1") (pin "38") (pinfunction "PA15_38") (pintype "passive"))
    )
    (net (code "63") (name "Net-(U1A-PH0-OSC_IN)") (class "Default")
      (node (ref "C8") (pin "1") (pinfunction "1_1") (pintype "passive"))
      (node (ref "U1") (pin "5") (pinfunction "PH0-OSC_IN_5") (pintype "passive"))
      (node (ref "X1") (pin "1") (pinfunction "1_1") (pintype "passive"))
    )
    (net (code "64") (name "Net-(U1A-PH1-OSC_IN)") (class "Default")
      (node (ref "C9") (pin "1") (pinfunction "1_1") (pintype "passive"))
      (node (ref "U1") (pin "6") (pinfunction "PH1-OSC_IN_6") (pintype "passive"))
      (node (ref "X1") (pin "3") (pinfunction "3_3") (pintype "passive"))
    )
    (net (code "65") (name "Net-(U1A-VCAP1)") (class "Default")
      (node (ref "C10") (pin "1") (pinfunction "1_1") (pintype "passive"))
      (node (ref "U1") (pin "22") (pinfunction "VCAP1_22") (pintype "passive"))
    )
    (net (code "66") (name "Net-(U2-ANT1)") (class "Default")
      (node (ref "L2") (pin "1") (pinfunction "1_1") (pintype "passive"))
      (node (ref "L3") (pin "1") (pinfunction "1_1") (pintype "passive"))
      (node (ref "U2") (pin "12") (pinfunction "ANT1_12") (pintype "passive"))
    )
    (net (code "67") (name "Net-(U2-ANT2)") (class "Default")
      (node (ref "L1") (pin "1") (pinfunction "1_1") (pintype "passive"))
      (node (ref "L2") (pin "2") (pinfunction "2_2") (pintype "passive"))
      (node (ref "U2") (pin "13") (pinfunction "ANT2_13") (pintype "passive"))
    )
    (net (code "68") (name "Net-(U2-IREF)") (class "Default")
      (node (ref "R3") (pin "1") (pinfunction "1_1") (pintype "passive"))
      (node (ref "U2") (pin "16") (pinfunction "IREF_16") (pintype "passive"))
    )
    (net (code "69") (name "Net-(U2-VDD_PA)") (class "Default")
      (node (ref "C6") (pin "2") (pinfunction "2_2") (pintype "passive"))
      (node (ref "C7") (pin "2") (pinfunction "2_2") (pintype "passive"))
      (node (ref "L3") (pin "2") (pinfunction "2_2") (pintype "passive"))
      (node (ref "U2") (pin "11") (pinfunction "VDD_PA_11") (pintype "passive"))
    )
    (net (code "70") (name "Net-(U2-XC1)") (class "Default")
      (node (ref "C12") (pin "2") (pinfunction "2_2") (pintype "passive"))
      (node (ref "U2") (pin "10") (pinfunction "XC1_10") (pintype "passive"))
      (node (ref "X2") (pin "3") (pinfunction "3_3") (pintype "passive"))
    )
    (net (code "71") (name "Net-(U2-XC2)") (class "Default")
      (node (ref "C11") (pin "2") (pinfunction "2_2") (pintype "passive"))
      (node (ref "U2") (pin "9") (pinfunction "XC2_9") (pintype "passive"))
      (node (ref "X2") (pin "1") (pinfunction "1_1") (pintype "passive"))
    )
    (net (code "72") (name "Net-(U3-CSB)") (class "Default")
      (node (ref "R12") (pin "1") (pinfunction "1_1") (pintype "passive"))
      (node (ref "U3") (pin "2") (pinfunction "CSB_2") (pintype "passive"))
    )
    (net (code "73") (name "Net-(U4-AD0)") (class "Default")
      (node (ref "R32") (pin "1") (pinfunction "1_1") (pintype "passive"))
      (node (ref "U4") (pin "9") (pinfunction "AD0_9") (pintype "passive"))
    )
    (net (code "74") (name "Net-(U4-CPOUT)") (class "Default")
      (node (ref "C22") (pin "2") (pinfunction "2_2") (pintype "passive"))
      (node (ref "U4") (pin "20") (pinfunction "CPOUT_20") (pintype "passive"))
    )
    (net (code "75") (name "Net-(U4-REGOUT)") (class "Default")
      (node (ref "C29") (pin "2") (pinfunction "2_2") (pintype "passive"))
      (node (ref "U4") (pin "10") (pinfunction "REGOUT_10") (pintype "passive"))
    )
    (net (code "76") (name "Net-(USB1-D+)") (class "Default")
      (node (ref "R20") (pin "1") (pinfunction "1_1") (pintype "passive"))
      (node (ref "USB1") (pin "3") (pinfunction "D+_3") (pintype "passive"))
    )
    (net (code "77") (name "Net-(USB1-D-)") (class "Default")
      (node (ref "R22") (pin "1") (pinfunction "1_1") (pintype "passive"))
      (node (ref "USB1") (pin "2") (pinfunction "D-_2") (pintype "passive"))
    )
    (net (code "78") (name "RF_3V3") (class "Default")
      (node (ref "C1") (pin "1") (pinfunction "1_1") (pintype "passive"))
      (node (ref "C2") (pin "1") (pinfunction "1_1") (pintype "passive"))
      (node (ref "C3") (pin "1") (pinfunction "1_1") (pintype "passive"))
      (node (ref "R14") (pin "2") (pinfunction "2_2") (pintype "passive"))
      (node (ref "U2") (pin "15") (pinfunction "VDD_15") (pintype "passive"))
      (node (ref "U2") (pin "18") (pinfunction "VDD_18") (pintype "passive"))
      (node (ref "U2") (pin "19") (pinfunction "DVDD_19") (pintype "passive"))
      (node (ref "U2") (pin "7") (pinfunction "VDD_7") (pintype "passive"))
    )
    (net (code "79") (name "RF_GND") (class "Default")
      (node (ref "C1") (pin "2") (pinfunction "2_2") (pintype "passive"))
      (node (ref "C11") (pin "1") (pinfunction "1_1") (pintype "passive"))
      (node (ref "C12") (pin "1") (pinfunction "1_1") (pintype "passive"))
      (node (ref "C2") (pin "2") (pinfunction "2_2") (pintype "passive"))
      (node (ref "C3") (pin "2") (pinfunction "2_2") (pintype "passive"))
      (node (ref "C5") (pin "1") (pinfunction "1_1") (pintype "passive"))
      (node (ref "C6") (pin "1") (pinfunction "1_1") (pintype "passive"))
      (node (ref "C7") (pin "1") (pinfunction "1_1") (pintype "passive"))
      (node (ref "R13") (pin "2") (pinfunction "2_2") (pintype "passive"))
      (node (ref "R3") (pin "2") (pinfunction "2_2") (pintype "passive"))
      (node (ref "U2") (pin "14") (pinfunction "VSS_14") (pintype "passive"))
      (node (ref "U2") (pin "17") (pinfunction "VSS_17") (pintype "passive"))
      (node (ref "U2") (pin "20") (pinfunction "VSS_20") (pintype "passive"))
      (node (ref "U2") (pin "8") (pinfunction "VSS_8") (pintype "passive"))
      (node (ref "X2") (pin "2") (pinfunction "2_2") (pintype "passive"))
      (node (ref "X2") (pin "4") (pinfunction "4_4") (pintype "passive"))
    )
    (net (code "80") (name "V3.3") (class "Default")
      (node (ref "C14") (pin "2") (pinfunction "2_2") (pintype "passive"))
      (node (ref "C15") (pin "2") (pinfunction "2_2") (pintype "passive"))
      (node (ref "C16") (pin "2") (pinfunction "2_2") (pintype "passive"))
      (node (ref "C17") (pin "2") (pinfunction "2_2") (pintype "passive"))
      (node (ref "C18") (pin "2") (pinfunction "2_2") (pintype "passive"))
      (node (ref "C26") (pin "1") (pinfunction "1_1") (pintype "passive"))
      (node (ref "C28") (pin "2") (pinfunction "2_2") (pintype "passive"))
      (node (ref "C31") (pin "2") (pinfunction "2_2") (pintype "passive"))
      (node (ref "JP1") (pin "7") (pinfunction "7_7") (pintype "passive"))
      (node (ref "JP2") (pin "6") (pinfunction "6_6") (pintype "passive"))
      (node (ref "LED1") (pin "1") (pinfunction "A_1") (pintype "passive"))
      (node (ref "LED2") (pin "1") (pinfunction "A_1") (pintype "passive"))
      (node (ref "LED3") (pin "1") (pinfunction "A_1") (pintype "passive"))
      (node (ref "LED4") (pin "1") (pinfunction "A_1") (pintype "passive"))
      (node (ref "LED5") (pin "1") (pinfunction "A_1") (pintype "passive"))
      (node (ref "LED6") (pin "1") (pinfunction "A_1") (pintype "passive"))
      (node (ref "R10") (pin "2") (pinfunction "2_2") (pintype "passive"))
      (node (ref "R11") (pin "2") (pinfunction "2_2") (pintype "passive"))
      (node (ref "R12") (pin "2") (pinfunction "2_2") (pintype "passive"))
      (node (ref "R14") (pin "1") (pinfunction "1_1") (pintype "passive"))
      (node (ref "R15") (pin "2") (pinfunction "2_2") (pintype "passive"))
      (node (ref "R21") (pin "2") (pinfunction "2_2") (pintype "passive"))
      (node (ref "R23") (pin "2") (pinfunction "2_2") (pintype "passive"))
      (node (ref "U1") (pin "1") (pinfunction "VBAT_1") (pintype "passive"))
      (node (ref "U1") (pin "24") (pinfunction "VDD_24") (pintype "passive"))
      (node (ref "U1") (pin "36") (pinfunction "VDD_36") (pintype "passive"))
      (node (ref "U1") (pin "48") (pinfunction "VDD_48") (pintype "passive"))
      (node (ref "U1") (pin "9") (pinfunction "VDDA/VREF+_9") (pintype "passive"))
      (node (ref "U3") (pin "6") (pinfunction "VddIO_6") (pintype "passive"))
      (node (ref "U3") (pin "8") (pinfunction "Vdd_8") (pintype "passive"))
      (node (ref "U4") (pin "13") (pinfunction "VDD_13") (pintype "passive"))
      (node (ref "U4") (pin "8") (pinfunction "VLOGIC_8") (pintype "passive"))
      (node (ref "V1") (pin "3") (pinfunction "VOUT_3") (pintype "passive"))
    )
    (net (code "81") (name "VBAT") (class "Default")
      (node (ref "C19") (pin "2") (pinfunction "2_2") (pintype "passive"))
      (node (ref "C20") (pin "2") (pinfunction "2_2") (pintype "passive"))
      (node (ref "C24") (pin "2") (pinfunction "2_2") (pintype "passive"))
      (node (ref "C25") (pin "2") (pinfunction "2_2") (pintype "passive"))
      (node (ref "C32") (pin "2") (pinfunction "2_2") (pintype "passive"))
      (node (ref "L4") (pin "1") (pinfunction "1_1") (pintype "passive"))
      (node (ref "M5") (pin "1") (pinfunction "1_1") (pintype "passive"))
      (node (ref "M6") (pin "1") (pinfunction "1_1") (pintype "passive"))
      (node (ref "M7") (pin "1") (pinfunction "1_1") (pintype "passive"))
      (node (ref "M8") (pin "1") (pinfunction "1_1") (pintype "passive"))
      (node (ref "R26") (pin "2") (pinfunction "2_2") (pintype "passive"))
      (node (ref "S1") (pin "2") (pinfunction "2_2") (pintype "passive"))
    )
    (net (code "82") (name "VCC") (class "Default")
      (node (ref "D1") (pin "1") (pinfunction "A_1") (pintype "passive"))
      (node (ref "USB1") (pin "1") (pinfunction "+5V_1") (pintype "passive"))
    )
    (net (code "83") (name "unconnected-(F1-Pad1)") (class "Default")
      (node (ref "F1") (pin "1") (pinfunction "1_1") (pintype "passive+no_connect"))
    )
    (net (code "84") (name "unconnected-(F2-Pad1)") (class "Default")
      (node (ref "F2") (pin "1") (pinfunction "1_1") (pintype "passive+no_connect"))
    )
    (net (code "85") (name "unconnected-(F3-Pad1)") (class "Default")
      (node (ref "F3") (pin "1") (pinfunction "1_1") (pintype "passive+no_connect"))
    )
    (net (code "86") (name "unconnected-(F4-Pad1)") (class "Default")
      (node (ref "F4") (pin "1") (pinfunction "1_1") (pintype "passive+no_connect"))
    )
    (net (code "87") (name "unconnected-(M1-Pad1)") (class "Default")
      (node (ref "M1") (pin "1") (pinfunction "1_1") (pintype "passive+no_connect"))
    )
    (net (code "88") (name "unconnected-(M2-Pad1)") (class "Default")
      (node (ref "M2") (pin "1") (pinfunction "1_1") (pintype "passive+no_connect"))
    )
    (net (code "89") (name "unconnected-(M3-Pad1)") (class "Default")
      (node (ref "M3") (pin "1") (pinfunction "1_1") (pintype "passive+no_connect"))
    )
    (net (code "90") (name "unconnected-(M4-Pad1)") (class "Default")
      (node (ref "M4") (pin "1") (pinfunction "1_1") (pintype "passive+no_connect"))
    )
    (net (code "91") (name "unconnected-(S1-Pad3)") (class "Default")
      (node (ref "S1") (pin "3") (pinfunction "3_3") (pintype "passive"))
    )
    (net (code "92") (name "unconnected-(U1A-PC14-OSC32_IN-Pad3)") (class "Default")
      (node (ref "U1") (pin "3") (pinfunction "PC14-OSC32_IN_3") (pintype "passive+no_connect"))
    )
    (net (code "93") (name "unconnected-(U1A-PC15-OSC32_OUT-Pad4)") (class "Default")
      (node (ref "U1") (pin "4") (pinfunction "PC15-OSC32_OUT_4") (pintype "passive+no_connect"))
    )
    (net (code "94") (name "unconnected-(U4-A-CL-Pad7)") (class "Default")
      (node (ref "U4") (pin "7") (pinfunction "A-CL_7") (pintype "passive+no_connect"))
    )
    (net (code "95") (name "unconnected-(U4-A_DA-Pad6)") (class "Default")
      (node (ref "U4") (pin "6") (pinfunction "A_DA_6") (pintype "passive+no_connect"))
    )
    (net (code "96") (name "unconnected-(U4-CLKOUT-Pad22)") (class "Default")
      (node (ref "U4") (pin "22") (pinfunction "CLKOUT_22") (pintype "passive+no_connect"))
    )
    (net (code "97") (name "unconnected-(U4-NC-Pad2)") (class "Default")
      (node (ref "U4") (pin "2") (pinfunction "NC_2") (pintype "passive+no_connect"))
    )
    (net (code "98") (name "unconnected-(U4-NC-Pad3)") (class "Default")
      (node (ref "U4") (pin "3") (pinfunction "NC_3") (pintype "passive+no_connect"))
    )
    (net (code "99") (name "unconnected-(U4-NC-Pad4)") (class "Default")
      (node (ref "U4") (pin "4") (pinfunction "NC_4") (pintype "passive+no_connect"))
    )
    (net (code "100") (name "unconnected-(U4-NC-Pad5)") (class "Default")
      (node (ref "U4") (pin "5") (pinfunction "NC_5") (pintype "passive+no_connect"))
    )
    (net (code "101") (name "unconnected-(U4-NC-Pad14)") (class "Default")
      (node (ref "U4") (pin "14") (pinfunction "NC_14") (pintype "passive+no_connect"))
    )
    (net (code "102") (name "unconnected-(U4-NC-Pad15)") (class "Default")
      (node (ref "U4") (pin "15") (pinfunction "NC_15") (pintype "passive+no_connect"))
    )
    (net (code "103") (name "unconnected-(U4-NC-Pad16)") (class "Default")
      (node (ref "U4") (pin "16") (pinfunction "NC_16") (pintype "passive+no_connect"))
    )
    (net (code "104") (name "unconnected-(U4-NC-Pad17)") (class "Default")
      (node (ref "U4") (pin "17") (pinfunction "NC_17") (pintype "passive+no_connect"))
    )
    (net (code "105") (name "unconnected-(U4-RESV-Pad19)") (class "Default")
      (node (ref "U4") (pin "19") (pinfunction "RESV_19") (pintype "passive+no_connect"))
    )
    (net (code "106") (name "unconnected-(U4-RESV-Pad21)") (class "Default")
      (node (ref "U4") (pin "21") (pinfunction "RESV_21") (pintype "passive+no_connect"))
    )
    (net (code "107") (name "unconnected-(USB1-ID-Pad4)") (class "Default")
      (node (ref "USB1") (pin "4") (pinfunction "ID_4") (pintype "passive+no_connect"))
    )
  )
)
